# test_filter.net
KiCad netlist of a schematic drawn in EAGLE
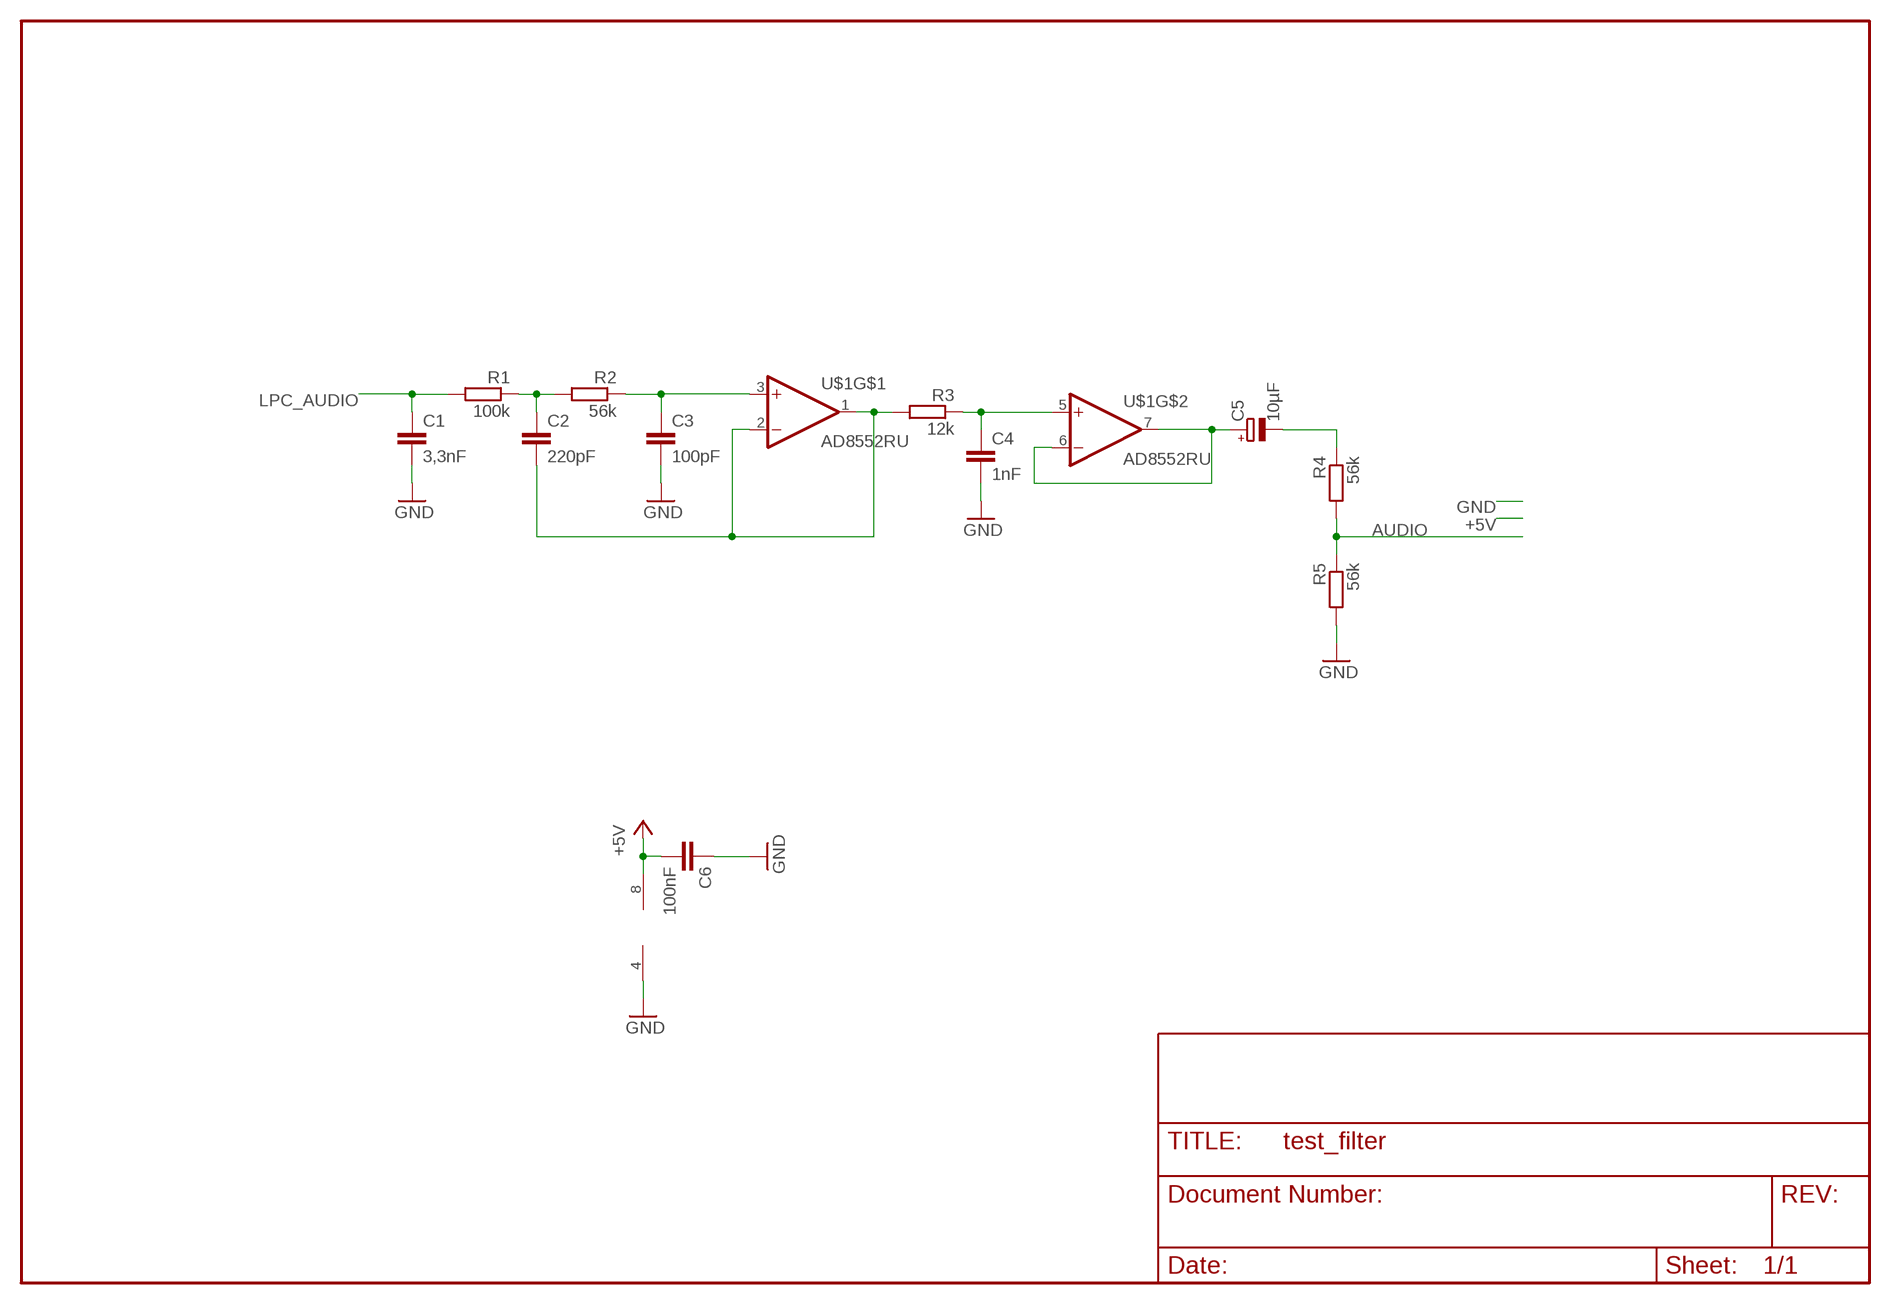
[diagram p0: schematic, sheet 1]

(export (version "E")
  (design (tool "Eeschema 10.0.6"))
  (components
    (comp (ref "C1")
      (value "3,3nF")
      (footprint "eagle-import:C050-030X075")
      (libsource (lib "eagle-import") (part "C-EU050-030X075"))
    )
    (comp (ref "C2")
      (value "220pF")
      (footprint "eagle-import:C050-030X075")
      (libsource (lib "eagle-import") (part "C-EU050-030X075"))
    )
    (comp (ref "C3")
      (value "100pF")
      (footprint "eagle-import:C050-030X075")
      (libsource (lib "eagle-import") (part "C-EU050-030X075"))
    )
    (comp (ref "C4")
      (value "1nF")
      (footprint "eagle-import:C050-030X075")
      (libsource (lib "eagle-import") (part "C-EU050-030X075"))
    )
    (comp (ref "C5")
      (value "10µF")
      (footprint "eagle-import:E2,5-7")
      (libsource (lib "eagle-import") (part "CPOL-EUE2.5-7"))
    )
    (comp (ref "C6")
      (value "100nF")
      (footprint "eagle-import:C050-030X075")
      (libsource (lib "eagle-import") (part "C-EU050-030X075"))
    )
    (comp (ref "R1")
      (value "100k")
      (footprint "eagle-import:0204_7")
      (libsource (lib "eagle-import") (part "R-EU_0204/7"))
    )
    (comp (ref "R2")
      (value "56k")
      (footprint "eagle-import:0204_7")
      (libsource (lib "eagle-import") (part "R-EU_0204/7"))
    )
    (comp (ref "R3")
      (value "12k")
      (footprint "eagle-import:0204_7")
      (libsource (lib "eagle-import") (part "R-EU_0204/7"))
    )
    (comp (ref "R4")
      (value "56k")
      (footprint "eagle-import:0204_7")
      (libsource (lib "eagle-import") (part "R-EU_0204/7"))
    )
    (comp (ref "R5")
      (value "56k")
      (footprint "eagle-import:0204_7")
      (libsource (lib "eagle-import") (part "R-EU_0204/7"))
    )
    (comp (ref "U$1")
      (value "AD8552RU")
      (footprint "eagle-import:TSSOP8")
      (libsource (lib "eagle-import") (part "AD8552RU"))
    )
  )
  (nets
    (net (code "1") (name "+5V") (class "Default")
      (node (ref "C6") (pin "2") (pinfunction "2_2") (pintype "passive"))
      (node (ref "U$1") (pin "8") (pinfunction "V+_8") (pintype "power_in"))
    )
    (net (code "2") (name "/AUDIO") (class "Default")
      (node (ref "R4") (pin "2") (pinfunction "2_2") (pintype "passive"))
      (node (ref "R5") (pin "1") (pinfunction "1_1") (pintype "passive"))
    )
    (net (code "3") (name "/LPC_AUDIO") (class "Default")
      (node (ref "C1") (pin "1") (pinfunction "1_1") (pintype "passive"))
      (node (ref "R1") (pin "2") (pinfunction "2_2") (pintype "passive"))
    )
    (net (code "4") (name "GND") (class "Default")
      (node (ref "C1") (pin "2") (pinfunction "2_2") (pintype "passive"))
      (node (ref "C3") (pin "2") (pinfunction "2_2") (pintype "passive"))
      (node (ref "C4") (pin "2") (pinfunction "2_2") (pintype "passive"))
      (node (ref "C6") (pin "1") (pinfunction "1_1") (pintype "passive"))
      (node (ref "R5") (pin "2") (pinfunction "2_2") (pintype "passive"))
      (node (ref "U$1") (pin "4") (pinfunction "V-_4") (pintype "power_in"))
    )
    (net (code "5") (name "Net-(C2-Pad1)") (class "Default")
      (node (ref "C2") (pin "1") (pinfunction "1_1") (pintype "passive"))
      (node (ref "R1") (pin "1") (pinfunction "1_1") (pintype "passive"))
      (node (ref "R2") (pin "2") (pinfunction "2_2") (pintype "passive"))
    )
    (net (code "6") (name "Net-(C5-Pad-)") (class "Default")
      (node (ref "C5") (pin "-") (pinfunction "-_-") (pintype "passive"))
      (node (ref "R4") (pin "1") (pinfunction "1_1") (pintype "passive"))
    )
    (net (code "7") (name "Net-(U$1A-+IN)") (class "Default")
      (node (ref "C3") (pin "1") (pinfunction "1_1") (pintype "passive"))
      (node (ref "R2") (pin "1") (pinfunction "1_1") (pintype "passive"))
      (node (ref "U$1") (pin "3") (pinfunction "+IN_3") (pintype "input"))
    )
    (net (code "8") (name "Net-(U$1A--IN)") (class "Default")
      (node (ref "C2") (pin "2") (pinfunction "2_2") (pintype "passive"))
      (node (ref "R3") (pin "2") (pinfunction "2_2") (pintype "passive"))
      (node (ref "U$1") (pin "1") (pinfunction "OUT_1") (pintype "output"))
      (node (ref "U$1") (pin "2") (pinfunction "-IN_2") (pintype "input"))
    )
    (net (code "9") (name "Net-(U$1B-+IN)") (class "Default")
      (node (ref "C4") (pin "1") (pinfunction "1_1") (pintype "passive"))
      (node (ref "R3") (pin "1") (pinfunction "1_1") (pintype "passive"))
      (node (ref "U$1") (pin "5") (pinfunction "+IN_5") (pintype "input"))
    )
    (net (code "10") (name "Net-(U$1B--IN)") (class "Default")
      (node (ref "C5") (pin "+") (pinfunction "+_+") (pintype "passive"))
      (node (ref "U$1") (pin "6") (pinfunction "-IN_6") (pintype "input"))
      (node (ref "U$1") (pin "7") (pinfunction "OUT_7") (pintype "output"))
    )
  )
)
